# tvac_systems_interface.net
KiCad netlist of a schematic drawn in EAGLE
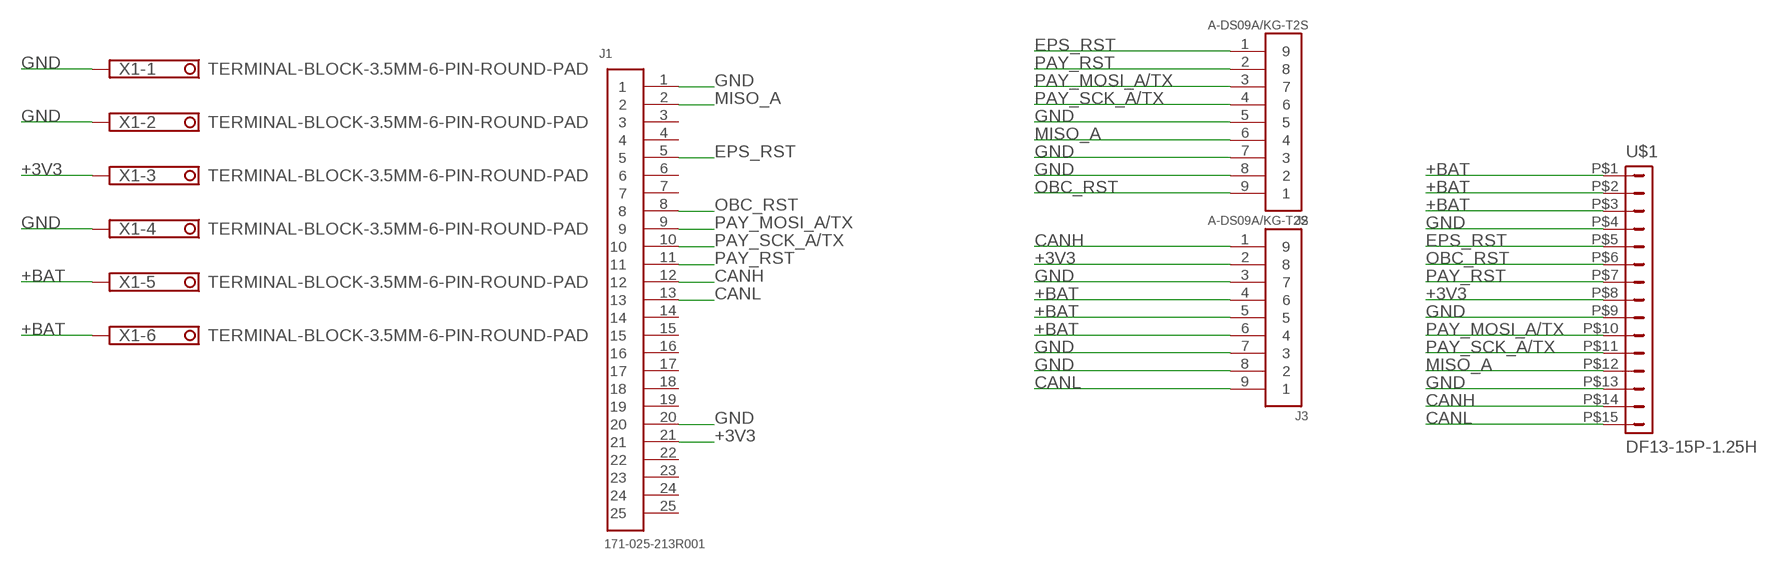
[diagram p0: schematic, sheet 1]

(export (version "E")
  (design (tool "Eeschema 10.0.6"))
  (components
    (comp (ref "J1")
      (value "171-025-213R001")
      (footprint "eagle-import:171-025-213R001")
      (fields
        (field (name "DIGIKEY_PART_NO") "4225FE-ND")
        (field (name "MANUFACTURER") "NorComp Inc.")
        (field (name "CREATED_BY") "PCBLayout.com")
      )
      (libsource (lib "eagle-import") (part "171-025-213R001"))
    )
    (comp (ref "J2")
      (value "A-DS09A/KG-T2S")
      (footprint "eagle-import:A-DS09A_KG-T2S")
      (fields
        (field (name "DIGI_KEY_PART_NUMBER") "AE10968-ND")
        (field (name "MANUFACTURER") "Assmann WSW Components")
        (field (name "MPN") "A-DS 09 A/KG-T2S")
        (field (name "CREATEDBY") "PCBLayout.com")
      )
      (libsource (lib "eagle-import") (part "A-DS09A/KG-T2S"))
    )
    (comp (ref "J3")
      (value "A-DS09A/KG-T2S")
      (footprint "eagle-import:A-DS09A_KG-T2S")
      (fields
        (field (name "DIGI_KEY_PART_NUMBER") "AE10968-ND")
        (field (name "MANUFACTURER") "Assmann WSW Components")
        (field (name "MPN") "A-DS 09 A/KG-T2S")
        (field (name "CREATEDBY") "PCBLayout.com")
      )
      (libsource (lib "eagle-import") (part "A-DS09A/KG-T2S"))
    )
    (comp (ref "U$1")
      (value "DF13-15P-1.25H")
      (footprint "eagle-import:DF13A-15P-1.25H")
      (libsource (lib "eagle-import") (part "DF13-15P-1.25H"))
    )
    (comp (ref "X1")
      (value "TERMINAL-BLOCK-3.5MM-6-PIN-ROUND-PAD")
      (footprint "eagle-import:TERMINAL-BLOCK-6-PIN-3.5MM-ROUND-PAD")
      (libsource (lib "eagle-import") (part "TERMINAL-BLOCK-3.5MM-6-PIN-ROUND-PAD"))
    )
  )
  (nets
    (net (code "1") (name "/+3V3") (class "Default")
      (node (ref "J1") (pin "21") (pinfunction "21_21") (pintype "passive"))
      (node (ref "J3") (pin "2") (pinfunction "8_2") (pintype "passive"))
      (node (ref "U$1") (pin "P$8") (pinfunction "8_P$8") (pintype "passive"))
      (node (ref "X1") (pin "3") (pinfunction "K_3") (pintype "passive"))
    )
    (net (code "2") (name "/+BAT") (class "Default")
      (node (ref "J3") (pin "4") (pinfunction "6_4") (pintype "passive"))
      (node (ref "J3") (pin "5") (pinfunction "5_5") (pintype "passive"))
      (node (ref "J3") (pin "6") (pinfunction "4_6") (pintype "passive"))
      (node (ref "U$1") (pin "P$1") (pinfunction "1_P$1") (pintype "passive"))
      (node (ref "U$1") (pin "P$2") (pinfunction "2_P$2") (pintype "passive"))
      (node (ref "U$1") (pin "P$3") (pinfunction "3_P$3") (pintype "passive"))
      (node (ref "X1") (pin "5") (pinfunction "K_5") (pintype "passive"))
      (node (ref "X1") (pin "6") (pinfunction "K_6") (pintype "passive"))
    )
    (net (code "3") (name "/CANH") (class "Default")
      (node (ref "J1") (pin "12") (pinfunction "12_12") (pintype "passive"))
      (node (ref "J3") (pin "1") (pinfunction "9_1") (pintype "passive"))
      (node (ref "U$1") (pin "P$14") (pinfunction "14_P$14") (pintype "passive"))
    )
    (net (code "4") (name "/CANL") (class "Default")
      (node (ref "J1") (pin "13") (pinfunction "13_13") (pintype "passive"))
      (node (ref "J3") (pin "9") (pinfunction "1_9") (pintype "passive"))
      (node (ref "U$1") (pin "P$15") (pinfunction "15_P$15") (pintype "passive"))
    )
    (net (code "5") (name "/EPS_RST") (class "Default")
      (node (ref "J1") (pin "5") (pinfunction "5_5") (pintype "passive"))
      (node (ref "J2") (pin "1") (pinfunction "9_1") (pintype "passive"))
      (node (ref "U$1") (pin "P$5") (pinfunction "5_P$5") (pintype "passive"))
    )
    (net (code "6") (name "/GND") (class "Default")
      (node (ref "J1") (pin "1") (pinfunction "1_1") (pintype "passive"))
      (node (ref "J1") (pin "20") (pinfunction "20_20") (pintype "passive"))
      (node (ref "J2") (pin "5") (pinfunction "5_5") (pintype "passive"))
      (node (ref "J2") (pin "7") (pinfunction "3_7") (pintype "passive"))
      (node (ref "J2") (pin "8") (pinfunction "2_8") (pintype "passive"))
      (node (ref "J3") (pin "3") (pinfunction "7_3") (pintype "passive"))
      (node (ref "J3") (pin "7") (pinfunction "3_7") (pintype "passive"))
      (node (ref "J3") (pin "8") (pinfunction "2_8") (pintype "passive"))
      (node (ref "U$1") (pin "P$13") (pinfunction "13_P$13") (pintype "passive"))
      (node (ref "U$1") (pin "P$4") (pinfunction "4_P$4") (pintype "passive"))
      (node (ref "U$1") (pin "P$9") (pinfunction "9_P$9") (pintype "passive"))
      (node (ref "X1") (pin "1") (pinfunction "K_1") (pintype "passive"))
      (node (ref "X1") (pin "2") (pinfunction "K_2") (pintype "passive"))
      (node (ref "X1") (pin "4") (pinfunction "K_4") (pintype "passive"))
    )
    (net (code "7") (name "/MISO_A") (class "Default")
      (node (ref "J1") (pin "2") (pinfunction "2_2") (pintype "passive"))
      (node (ref "J2") (pin "6") (pinfunction "4_6") (pintype "passive"))
      (node (ref "U$1") (pin "P$12") (pinfunction "12_P$12") (pintype "passive"))
    )
    (net (code "8") (name "/OBC_RST") (class "Default")
      (node (ref "J1") (pin "8") (pinfunction "8_8") (pintype "passive"))
      (node (ref "J2") (pin "9") (pinfunction "1_9") (pintype "passive"))
      (node (ref "U$1") (pin "P$6") (pinfunction "6_P$6") (pintype "passive"))
    )
    (net (code "9") (name "/PAY_MOSI_A{slash}TX") (class "Default")
      (node (ref "J1") (pin "9") (pinfunction "9_9") (pintype "passive"))
      (node (ref "J2") (pin "3") (pinfunction "7_3") (pintype "passive"))
      (node (ref "U$1") (pin "P$10") (pinfunction "10_P$10") (pintype "passive"))
    )
    (net (code "10") (name "/PAY_RST") (class "Default")
      (node (ref "J1") (pin "11") (pinfunction "11_11") (pintype "passive"))
      (node (ref "J2") (pin "2") (pinfunction "8_2") (pintype "passive"))
      (node (ref "U$1") (pin "P$7") (pinfunction "7_P$7") (pintype "passive"))
    )
    (net (code "11") (name "/PAY_SCK_A{slash}TX") (class "Default")
      (node (ref "J1") (pin "10") (pinfunction "10_10") (pintype "passive"))
      (node (ref "J2") (pin "4") (pinfunction "6_4") (pintype "passive"))
      (node (ref "U$1") (pin "P$11") (pinfunction "11_P$11") (pintype "passive"))
    )
    (net (code "12") (name "unconnected-(J1-Pad3)") (class "Default")
      (node (ref "J1") (pin "3") (pinfunction "3_3") (pintype "passive"))
    )
    (net (code "13") (name "unconnected-(J1-Pad4)") (class "Default")
      (node (ref "J1") (pin "4") (pinfunction "4_4") (pintype "passive"))
    )
    (net (code "14") (name "unconnected-(J1-Pad6)") (class "Default")
      (node (ref "J1") (pin "6") (pinfunction "6_6") (pintype "passive"))
    )
    (net (code "15") (name "unconnected-(J1-Pad7)") (class "Default")
      (node (ref "J1") (pin "7") (pinfunction "7_7") (pintype "passive"))
    )
    (net (code "16") (name "unconnected-(J1-Pad14)") (class "Default")
      (node (ref "J1") (pin "14") (pinfunction "14_14") (pintype "passive"))
    )
    (net (code "17") (name "unconnected-(J1-Pad15)") (class "Default")
      (node (ref "J1") (pin "15") (pinfunction "15_15") (pintype "passive"))
    )
    (net (code "18") (name "unconnected-(J1-Pad16)") (class "Default")
      (node (ref "J1") (pin "16") (pinfunction "16_16") (pintype "passive"))
    )
    (net (code "19") (name "unconnected-(J1-Pad17)") (class "Default")
      (node (ref "J1") (pin "17") (pinfunction "17_17") (pintype "passive"))
    )
    (net (code "20") (name "unconnected-(J1-Pad18)") (class "Default")
      (node (ref "J1") (pin "18") (pinfunction "18_18") (pintype "passive"))
    )
    (net (code "21") (name "unconnected-(J1-Pad19)") (class "Default")
      (node (ref "J1") (pin "19") (pinfunction "19_19") (pintype "passive"))
    )
    (net (code "22") (name "unconnected-(J1-Pad22)") (class "Default")
      (node (ref "J1") (pin "22") (pinfunction "22_22") (pintype "passive"))
    )
    (net (code "23") (name "unconnected-(J1-Pad23)") (class "Default")
      (node (ref "J1") (pin "23") (pinfunction "23_23") (pintype "passive"))
    )
    (net (code "24") (name "unconnected-(J1-Pad24)") (class "Default")
      (node (ref "J1") (pin "24") (pinfunction "24_24") (pintype "passive"))
    )
    (net (code "25") (name "unconnected-(J1-Pad25)") (class "Default")
      (node (ref "J1") (pin "25") (pinfunction "25_25") (pintype "passive"))
    )
  )
)
